# COF.net
KiCad netlist of a schematic drawn in Altium Designer
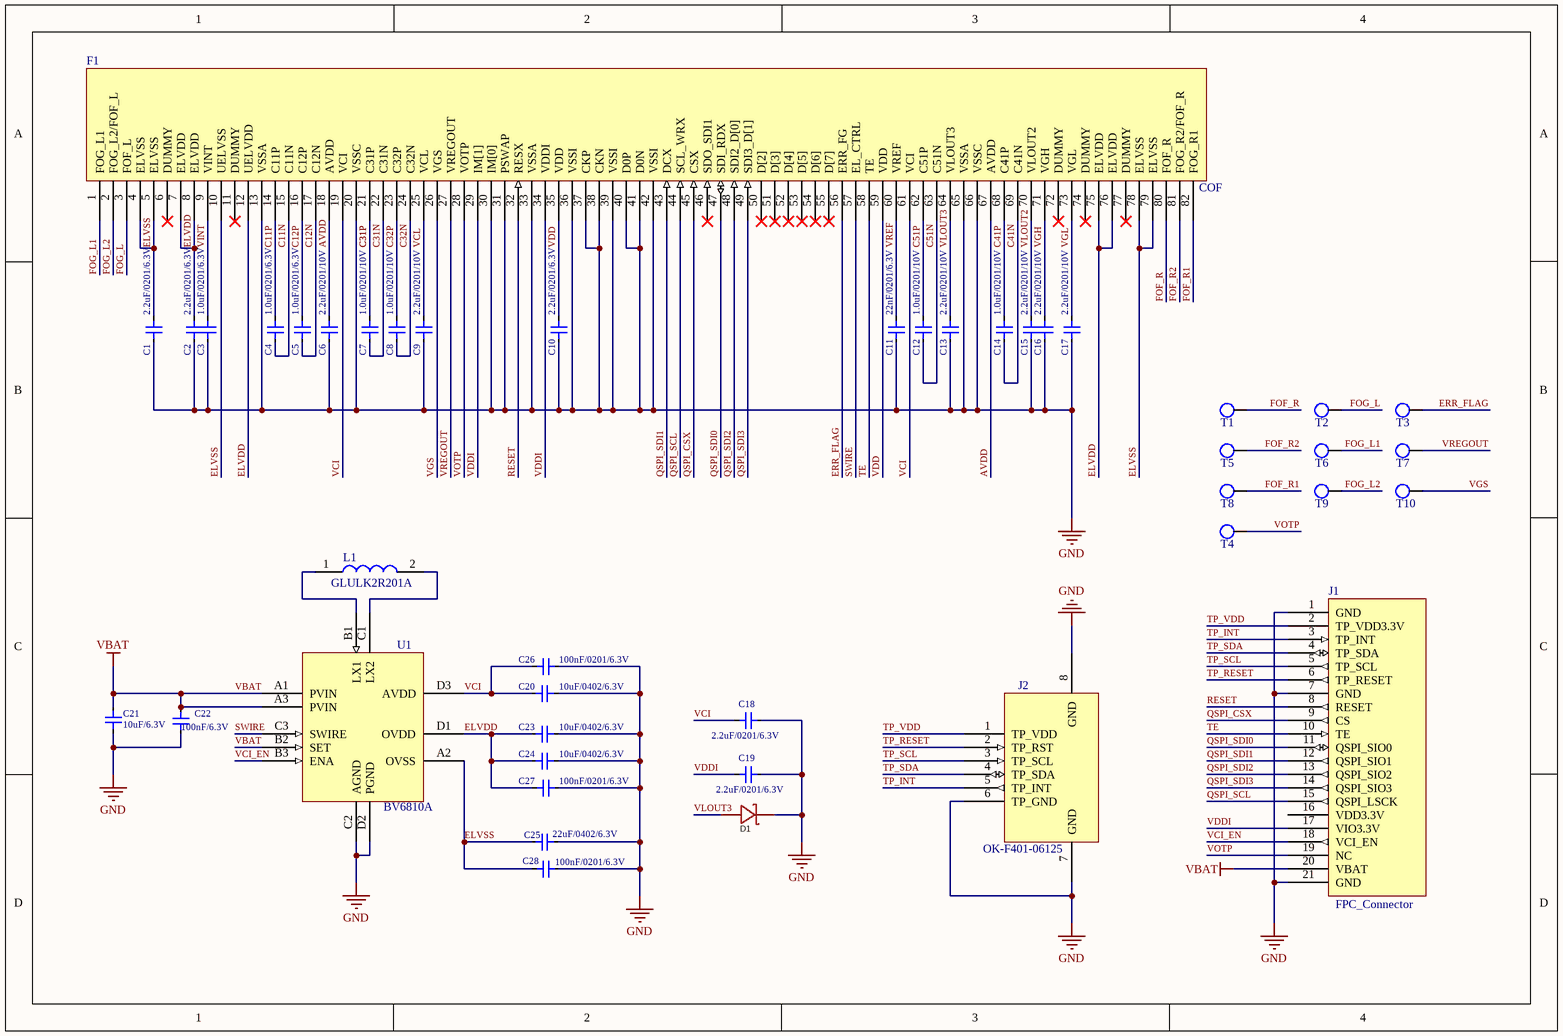
[diagram p0: COF.SchDoc]

(export (version "E")
  (design (tool "Eeschema 10.0.6"))
  (components
    (comp (ref "C1")
      (value "2.2uF/0201/6.3V")
      (footprint "CAPC0603X33N")
      (description "NONE")
      (fields
        (field (name "MANUFACTURER") "Murata")
        (field (name "MANUFACTURER PART NUMBER") "GRM033R61A105ME15D")
      )
      (libsource (lib "COF") (part "Capacitor"))
    )
    (comp (ref "C2")
      (value "2.2uF/0201/6.3V")
      (footprint "CAPC0603X33N")
      (description "NONE")
      (fields
        (field (name "MANUFACTURER") "Murata")
        (field (name "MANUFACTURER PART NUMBER") "GRM033R61A105ME15D")
      )
      (libsource (lib "COF") (part "Capacitor"))
    )
    (comp (ref "C3")
      (value "1.0uF/0201/6.3V")
      (footprint "CAPC0603X33N")
      (description "NONE")
      (fields
        (field (name "MANUFACTURER") "Murata")
        (field (name "MANUFACTURER PART NUMBER") "GRM033R61A105ME15D")
      )
      (libsource (lib "COF") (part "Capacitor"))
    )
    (comp (ref "C4")
      (value "1.0uF/0201/6.3V")
      (footprint "CAPC0603X33N")
      (description "NONE")
      (fields
        (field (name "MANUFACTURER") "Murata")
        (field (name "MANUFACTURER PART NUMBER") "GRM033R61A105ME15D")
      )
      (libsource (lib "COF") (part "Capacitor"))
    )
    (comp (ref "C5")
      (value "1.0uF/0201/6.3V")
      (footprint "CAPC0603X33N")
      (description "NONE")
      (fields
        (field (name "MANUFACTURER") "Murata")
        (field (name "MANUFACTURER PART NUMBER") "GRM033R61A105ME15D")
      )
      (libsource (lib "COF") (part "Capacitor"))
    )
    (comp (ref "C6")
      (value "2.2uF/0201/10V")
      (footprint "CAPC0603X33N")
      (description "NONE")
      (fields
        (field (name "MANUFACTURER") "Murata")
        (field (name "MANUFACTURER PART NUMBER") "GRM033R61A105ME15D")
      )
      (libsource (lib "COF") (part "Capacitor"))
    )
    (comp (ref "C7")
      (value "1.0uF/0201/10V")
      (footprint "CAPC0603X33N")
      (description "NONE")
      (fields
        (field (name "MANUFACTURER") "Murata")
        (field (name "MANUFACTURER PART NUMBER") "GRM033R61A105ME15D")
      )
      (libsource (lib "COF") (part "Capacitor"))
    )
    (comp (ref "C8")
      (value "1.0uF/0201/10V")
      (footprint "CAPC0603X33N")
      (description "NONE")
      (fields
        (field (name "MANUFACTURER") "Murata")
        (field (name "MANUFACTURER PART NUMBER") "GRM033R61A105ME15D")
      )
      (libsource (lib "COF") (part "Capacitor"))
    )
    (comp (ref "C9")
      (value "2.2uF/0201/10V")
      (footprint "CAPC0603X33N")
      (description "NONE")
      (fields
        (field (name "MANUFACTURER") "Murata")
        (field (name "MANUFACTURER PART NUMBER") "GRM033R61A105ME15D")
      )
      (libsource (lib "COF") (part "Capacitor"))
    )
    (comp (ref "C10")
      (value "2.2uF/0201/6.3V")
      (footprint "CAPC0603X33N")
      (description "NONE")
      (fields
        (field (name "MANUFACTURER") "Murata")
        (field (name "MANUFACTURER PART NUMBER") "GRM033R61A105ME15D")
      )
      (libsource (lib "COF") (part "Capacitor"))
    )
    (comp (ref "C11")
      (value "22nF/0201/6.3V")
      (footprint "CAPC0603X33N")
      (description "NONE")
      (fields
        (field (name "MANUFACTURER") "Murata")
        (field (name "MANUFACTURER PART NUMBER") "GRM033R61A105ME15D")
      )
      (libsource (lib "COF") (part "Capacitor"))
    )
    (comp (ref "C12")
      (value "1.0uF/0201/10V")
      (footprint "CAPC0603X33N")
      (description "NONE")
      (fields
        (field (name "MANUFACTURER") "Murata")
        (field (name "MANUFACTURER PART NUMBER") "GRM033R61A105ME15D")
      )
      (libsource (lib "COF") (part "Capacitor"))
    )
    (comp (ref "C13")
      (value "2.2uF/0201/10V")
      (footprint "CAPC0603X33N")
      (description "NONE")
      (fields
        (field (name "MANUFACTURER") "Murata")
        (field (name "MANUFACTURER PART NUMBER") "GRM033R61A105ME15D")
      )
      (libsource (lib "COF") (part "Capacitor"))
    )
    (comp (ref "C14")
      (value "1.0uF/0201/10V")
      (footprint "CAPC0603X33N")
      (description "NONE")
      (fields
        (field (name "MANUFACTURER") "Murata")
        (field (name "MANUFACTURER PART NUMBER") "GRM033R61A105ME15D")
      )
      (libsource (lib "COF") (part "Capacitor"))
    )
    (comp (ref "C15")
      (value "2.2uF/0201/10V")
      (footprint "CAPC0603X33N")
      (description "NONE")
      (fields
        (field (name "MANUFACTURER") "Murata")
        (field (name "MANUFACTURER PART NUMBER") "GRM033R61A105ME15D")
      )
      (libsource (lib "COF") (part "Capacitor"))
    )
    (comp (ref "C16")
      (value "2.2uF/0201/10V")
      (footprint "CAPC0603X33N")
      (description "NONE")
      (fields
        (field (name "MANUFACTURER") "Murata")
        (field (name "MANUFACTURER PART NUMBER") "GRM033R61A105ME15D")
      )
      (libsource (lib "COF") (part "Capacitor"))
    )
    (comp (ref "C17")
      (value "2.2uF/0201/10V")
      (footprint "CAPC0603X33N")
      (description "NONE")
      (fields
        (field (name "MANUFACTURER") "Murata")
        (field (name "MANUFACTURER PART NUMBER") "GRM033R61A105ME15D")
      )
      (libsource (lib "COF") (part "Capacitor"))
    )
    (comp (ref "C18")
      (value "2.2uF/0201/6.3V")
      (footprint "CAPC0603X33N")
      (description "NONE")
      (fields
        (field (name "MANUFACTURER") "Murata")
        (field (name "MANUFACTURER PART NUMBER") "GRM033R61A105ME15D")
      )
      (libsource (lib "COF") (part "Capacitor"))
    )
    (comp (ref "C19")
      (value "2.2uF/0201/6.3V")
      (footprint "CAPC0603X33N")
      (description "NONE")
      (fields
        (field (name "MANUFACTURER") "Murata")
        (field (name "MANUFACTURER PART NUMBER") "GRM033R61A105ME15D")
      )
      (libsource (lib "COF") (part "Capacitor"))
    )
    (comp (ref "C20")
      (value "10uF/0402/6.3V")
      (footprint "CAPC1005X57N")
      (description "NONE")
      (fields
        (field (name "MANUFACTURER") "Murata")
        (field (name "MANUFACTURER PART NUMBER") "GRM033R61A105ME15D")
      )
      (libsource (lib "COF") (part "Capacitor"))
    )
    (comp (ref "C21")
      (value "10uF/6.3V")
      (footprint "CAPC1005X57N")
      (description "NONE")
      (fields
        (field (name "MANUFACTURER") "Murata")
        (field (name "MANUFACTURER PART NUMBER") "GRM033R61A105ME15D")
      )
      (libsource (lib "COF") (part "Capacitor"))
    )
    (comp (ref "C22")
      (value "100nF/6.3V")
      (footprint "CAPC0603X33N")
      (description "NONE")
      (fields
        (field (name "MANUFACTURER") "Murata")
        (field (name "MANUFACTURER PART NUMBER") "GRM033R61A105ME15D")
      )
      (libsource (lib "COF") (part "Capacitor"))
    )
    (comp (ref "C23")
      (value "10uF/0402/6.3V")
      (footprint "CAPC1005X57N")
      (description "NONE")
      (fields
        (field (name "MANUFACTURER") "Murata")
        (field (name "MANUFACTURER PART NUMBER") "GRM033R61A105ME15D")
      )
      (libsource (lib "COF") (part "Capacitor"))
    )
    (comp (ref "C24")
      (value "10uF/0402/6.3V")
      (footprint "CAPC1005X57N")
      (description "NONE")
      (fields
        (field (name "MANUFACTURER") "Murata")
        (field (name "MANUFACTURER PART NUMBER") "GRM033R61A105ME15D")
      )
      (libsource (lib "COF") (part "Capacitor"))
    )
    (comp (ref "C25")
      (value "22uF/0402/6.3V")
      (footprint "CAPC1005X57N")
      (description "NONE")
      (fields
        (field (name "MANUFACTURER") "Murata")
        (field (name "MANUFACTURER PART NUMBER") "GRM033R61A105ME15D")
      )
      (libsource (lib "COF") (part "Capacitor"))
    )
    (comp (ref "C26")
      (value "100nF/0201/6.3V")
      (footprint "CAPC0603X33N")
      (description "NONE")
      (fields
        (field (name "MANUFACTURER") "Murata")
        (field (name "MANUFACTURER PART NUMBER") "GRM033R61A105ME15D")
      )
      (libsource (lib "COF") (part "Capacitor"))
    )
    (comp (ref "C27")
      (value "100nF/0201/6.3V")
      (footprint "CAPC0603X33N")
      (description "NONE")
      (fields
        (field (name "MANUFACTURER") "Murata")
        (field (name "MANUFACTURER PART NUMBER") "GRM033R61A105ME15D")
      )
      (libsource (lib "COF") (part "Capacitor"))
    )
    (comp (ref "C28")
      (value "100nF/0201/6.3V")
      (footprint "CAPC0603X33N")
      (description "NONE")
      (fields
        (field (name "MANUFACTURER") "Murata")
        (field (name "MANUFACTURER PART NUMBER") "GRM033R61A105ME15D")
      )
      (libsource (lib "COF") (part "Capacitor"))
    )
    (comp (ref "D1")
      (value "LDSR01S30ST5G")
      (footprint "DFN0603-D_L0.6-W0.3-P0.34-RD")
      (fields (field (name "MANUFACTURER") "LRC(乐山无线电)"))
      (libsource (lib "COF") (part "LDSR01S30ST5G"))
    )
    (comp (ref "F1") (value "COF") (footprint "COF Connector") (libsource (lib "COF") (part "COF")))
    (comp (ref "J1")
      (value "FPC_Connector")
      (footprint "FPC Connector")
      (libsource (lib "COF") (part "21Pin_Connector"))
    )
    (comp (ref "J2")
      (value "OK-F401-06125")
      (footprint "FFC-SMD_6P-P0.50_FH34SRJ-6S-0.5SH")
      (libsource (lib "COF") (part "OK-F401-06125"))
    )
    (comp (ref "L1")
      (value "GLULK2R201A")
      (footprint "MPL2012S2R2MDT")
      (description "Inductor")
      (fields
        (field (name "MANUFACTURER_PART_NUMBER") "LQM2MPN2R2NG0L")
        (field (name "MOUSER PART NUMBER") "81-LQM2MPN2R2NG0L")
      )
      (libsource (lib "COF") (part "GLULK2R201A"))
    )
    (comp (ref "T1")
      (value "Test_Point")
      (footprint "TP-C045-PI")
      (libsource (lib "COF") (part "Test_Point"))
    )
    (comp (ref "T2")
      (value "Test_Point")
      (footprint "TP-C045-PI")
      (libsource (lib "COF") (part "Test_Point"))
    )
    (comp (ref "T3")
      (value "Test_Point")
      (footprint "TP-C045-PI")
      (libsource (lib "COF") (part "Test_Point"))
    )
    (comp (ref "T4")
      (value "Test_Point")
      (footprint "TP-C045-PI")
      (libsource (lib "COF") (part "Test_Point"))
    )
    (comp (ref "T5")
      (value "Test_Point")
      (footprint "TP-C045-PI")
      (libsource (lib "COF") (part "Test_Point"))
    )
    (comp (ref "T6")
      (value "Test_Point")
      (footprint "TP-C045-PI")
      (libsource (lib "COF") (part "Test_Point"))
    )
    (comp (ref "T7")
      (value "Test_Point")
      (footprint "TP-C045-PI")
      (libsource (lib "COF") (part "Test_Point"))
    )
    (comp (ref "T8")
      (value "Test_Point")
      (footprint "TP-C045-PI")
      (libsource (lib "COF") (part "Test_Point"))
    )
    (comp (ref "T9")
      (value "Test_Point")
      (footprint "TP-C045-PI")
      (libsource (lib "COF") (part "Test_Point"))
    )
    (comp (ref "T10")
      (value "Test_Point")
      (footprint "TP-C045-PI")
      (libsource (lib "COF") (part "Test_Point"))
    )
    (comp (ref "U1")
      (value "BV6810A")
      (footprint "WLCSP-12_L1.7-W1.5-R4-C3-P0.40-TL-1")
      (libsource (lib "COF") (part "BV6810A"))
    )
  )
  (nets
    (net (code "1") (name "/AVDD") (class "Default")
      (node (ref "C6") (pin "1") (pinfunction "1_1") (pintype "passive"))
      (node (ref "F1") (pin "18") (pinfunction "AVDD_18") (pintype "power_in"))
      (node (ref "F1") (pin "67") (pinfunction "AVDD_67") (pintype "power_in"))
    )
    (net (code "2") (name "/C11N") (class "Default")
      (node (ref "C4") (pin "2") (pinfunction "2_2") (pintype "passive"))
      (node (ref "F1") (pin "15") (pinfunction "C11N_15") (pintype "tri_state"))
    )
    (net (code "3") (name "/C11P") (class "Default")
      (node (ref "C4") (pin "1") (pinfunction "1_1") (pintype "passive"))
      (node (ref "F1") (pin "14") (pinfunction "C11P_14") (pintype "tri_state"))
    )
    (net (code "4") (name "/C12N") (class "Default")
      (node (ref "C5") (pin "2") (pinfunction "2_2") (pintype "passive"))
      (node (ref "F1") (pin "17") (pinfunction "C12N_17") (pintype "tri_state"))
    )
    (net (code "5") (name "/C12P") (class "Default")
      (node (ref "C5") (pin "1") (pinfunction "1_1") (pintype "passive"))
      (node (ref "F1") (pin "16") (pinfunction "C12P_16") (pintype "tri_state"))
    )
    (net (code "6") (name "/C31N") (class "Default")
      (node (ref "C7") (pin "2") (pinfunction "2_2") (pintype "passive"))
      (node (ref "F1") (pin "22") (pinfunction "C31N_22") (pintype "tri_state"))
    )
    (net (code "7") (name "/C31P") (class "Default")
      (node (ref "C7") (pin "1") (pinfunction "1_1") (pintype "passive"))
      (node (ref "F1") (pin "21") (pinfunction "C31P_21") (pintype "tri_state"))
    )
    (net (code "8") (name "/C32N") (class "Default")
      (node (ref "C8") (pin "2") (pinfunction "2_2") (pintype "passive"))
      (node (ref "F1") (pin "24") (pinfunction "C32N_24") (pintype "tri_state"))
    )
    (net (code "9") (name "/C32P") (class "Default")
      (node (ref "C8") (pin "1") (pinfunction "1_1") (pintype "passive"))
      (node (ref "F1") (pin "23") (pinfunction "C32P_23") (pintype "tri_state"))
    )
    (net (code "10") (name "/C41N") (class "Default")
      (node (ref "C14") (pin "2") (pinfunction "2_2") (pintype "passive"))
      (node (ref "F1") (pin "69") (pinfunction "C41N_69") (pintype "tri_state"))
    )
    (net (code "11") (name "/C41P") (class "Default")
      (node (ref "C14") (pin "1") (pinfunction "1_1") (pintype "passive"))
      (node (ref "F1") (pin "68") (pinfunction "C41P_68") (pintype "tri_state"))
    )
    (net (code "12") (name "/C51N") (class "Default")
      (node (ref "C12") (pin "2") (pinfunction "2_2") (pintype "passive"))
      (node (ref "F1") (pin "63") (pinfunction "C51N_63") (pintype "tri_state"))
    )
    (net (code "13") (name "/C51P") (class "Default")
      (node (ref "C12") (pin "1") (pinfunction "1_1") (pintype "passive"))
      (node (ref "F1") (pin "62") (pinfunction "C51P_62") (pintype "tri_state"))
    )
    (net (code "14") (name "/ELVDD") (class "Default")
      (node (ref "C2") (pin "1") (pinfunction "1_1") (pintype "passive"))
      (node (ref "C23") (pin "2") (pinfunction "2_2") (pintype "passive"))
      (node (ref "C24") (pin "2") (pinfunction "2_2") (pintype "passive"))
      (node (ref "C27") (pin "1") (pinfunction "1_1") (pintype "passive"))
      (node (ref "F1") (pin "12") (pinfunction "UELVDD_12") (pintype "power_in"))
      (node (ref "F1") (pin "7") (pinfunction "ELVDD_7") (pintype "power_in"))
      (node (ref "F1") (pin "75") (pinfunction "ELVDD_75") (pintype "power_in"))
      (node (ref "F1") (pin "76") (pinfunction "ELVDD_76") (pintype "power_in"))
      (node (ref "F1") (pin "8") (pinfunction "ELVDD_8") (pintype "power_in"))
      (node (ref "U1") (pin "D1") (pinfunction "OVDD_D1") (pintype "power_in"))
    )
    (net (code "15") (name "/ELVSS") (class "Default")
      (node (ref "C1") (pin "1") (pinfunction "1_1") (pintype "passive"))
      (node (ref "C25") (pin "2") (pinfunction "2_2") (pintype "passive"))
      (node (ref "C28") (pin "1") (pinfunction "1_1") (pintype "passive"))
      (node (ref "F1") (pin "10") (pinfunction "UELVSS_10") (pintype "power_in"))
      (node (ref "F1") (pin "4") (pinfunction "ELVSS_4") (pintype "power_in"))
      (node (ref "F1") (pin "5") (pinfunction "ELVSS_5") (pintype "power_in"))
      (node (ref "F1") (pin "78") (pinfunction "ELVSS_78") (pintype "power_in"))
      (node (ref "F1") (pin "79") (pinfunction "ELVSS_79") (pintype "power_in"))
      (node (ref "U1") (pin "A2") (pinfunction "OVSS_A2") (pintype "power_in"))
    )
    (net (code "16") (name "/ERR_FLAG") (class "Default")
      (node (ref "F1") (pin "56") (pinfunction "ERR_FG_56") (pintype "tri_state"))
      (node (ref "T3") (pin "1") (pinfunction "1_1") (pintype "passive"))
    )
    (net (code "17") (name "/FOF_R") (class "Default")
      (node (ref "F1") (pin "80") (pinfunction "FOF_R_80") (pintype "tri_state"))
      (node (ref "T1") (pin "1") (pinfunction "1_1") (pintype "passive"))
    )
    (net (code "18") (name "/FOF_R1") (class "Default")
      (node (ref "F1") (pin "82") (pinfunction "FOG_R1_82") (pintype "tri_state"))
      (node (ref "T8") (pin "1") (pinfunction "1_1") (pintype "passive"))
    )
    (net (code "19") (name "/FOF_R2") (class "Default")
      (node (ref "F1") (pin "81") (pinfunction "FOG_R2/FOF_R_81") (pintype "tri_state"))
      (node (ref "T5") (pin "1") (pinfunction "1_1") (pintype "passive"))
    )
    (net (code "20") (name "/FOG_L") (class "Default")
      (node (ref "F1") (pin "3") (pinfunction "FOF_L_3") (pintype "tri_state"))
      (node (ref "T2") (pin "1") (pinfunction "1_1") (pintype "passive"))
    )
    (net (code "21") (name "/FOG_L1") (class "Default")
      (node (ref "F1") (pin "1") (pinfunction "FOG_L1_1") (pintype "tri_state"))
      (node (ref "T6") (pin "1") (pinfunction "1_1") (pintype "passive"))
    )
    (net (code "22") (name "/FOG_L2") (class "Default")
      (node (ref "F1") (pin "2") (pinfunction "FOG_L2/FOF_L_2") (pintype "tri_state"))
      (node (ref "T9") (pin "1") (pinfunction "1_1") (pintype "passive"))
    )
    (net (code "23") (name "/QSPI_CSX") (class "Default")
      (node (ref "F1") (pin "45") (pinfunction "CSX_45") (pintype "input"))
      (node (ref "J1") (pin "9") (pinfunction "CS_9") (pintype "output"))
    )
    (net (code "24") (name "/QSPI_SCL") (class "Default")
      (node (ref "F1") (pin "44") (pinfunction "SCL_WRX_44") (pintype "input"))
      (node (ref "J1") (pin "15") (pinfunction "QSPI_LSCK_15") (pintype "output"))
    )
    (net (code "25") (name "/QSPI_SDI0") (class "Default")
      (node (ref "F1") (pin "47") (pinfunction "SDI_RDX_47") (pintype "bidirectional"))
      (node (ref "J1") (pin "11") (pinfunction "QSPI_SIO0_11") (pintype "bidirectional"))
    )
    (net (code "26") (name "/QSPI_SDI1") (class "Default")
      (node (ref "F1") (pin "43") (pinfunction "DCX_43") (pintype "input"))
      (node (ref "J1") (pin "12") (pinfunction "QSPI_SIO1_12") (pintype "output"))
    )
    (net (code "27") (name "/QSPI_SDI2") (class "Default")
      (node (ref "F1") (pin "48") (pinfunction "SDI2_D[0]_48") (pintype "input"))
      (node (ref "J1") (pin "13") (pinfunction "QSPI_SIO2_13") (pintype "output"))
    )
    (net (code "28") (name "/QSPI_SDI3") (class "Default")
      (node (ref "F1") (pin "49") (pinfunction "SDI3_D[1]_49") (pintype "input"))
      (node (ref "J1") (pin "14") (pinfunction "QSPI_SIO3_14") (pintype "output"))
    )
    (net (code "29") (name "/RESET") (class "Default")
      (node (ref "F1") (pin "32") (pinfunction "RESX_32") (pintype "input"))
      (node (ref "J1") (pin "8") (pinfunction "RESET_8") (pintype "output"))
    )
    (net (code "30") (name "/SWIRE") (class "Default")
      (node (ref "F1") (pin "57") (pinfunction "EL_CTRL_57") (pintype "tri_state"))
      (node (ref "U1") (pin "C3") (pinfunction "SWIRE_C3") (pintype "input"))
    )
    (net (code "31") (name "/TE") (class "Default")
      (node (ref "F1") (pin "58") (pinfunction "TE_58") (pintype "tri_state"))
      (node (ref "J1") (pin "10") (pinfunction "TE_10") (pintype "input"))
    )
    (net (code "32") (name "/TP_INT") (class "Default")
      (node (ref "J1") (pin "3") (pinfunction "TP_INT_3") (pintype "input"))
      (node (ref "J2") (pin "5") (pinfunction "TP_INT_5") (pintype "output"))
    )
    (net (code "33") (name "/TP_RESET") (class "Default")
      (node (ref "J1") (pin "6") (pinfunction "TP_RESET_6") (pintype "output"))
      (node (ref "J2") (pin "2") (pinfunction "TP_RST_2") (pintype "input"))
    )
    (net (code "34") (name "/TP_SCL") (class "Default")
      (node (ref "J1") (pin "5") (pinfunction "TP_SCL_5") (pintype "output"))
      (node (ref "J2") (pin "3") (pinfunction "TP_SCL_3") (pintype "input"))
    )
    (net (code "35") (name "/TP_SDA") (class "Default")
      (node (ref "J1") (pin "4") (pinfunction "TP_SDA_4") (pintype "bidirectional"))
      (node (ref "J2") (pin "4") (pinfunction "TP_SDA_4") (pintype "bidirectional"))
    )
    (net (code "36") (name "/TP_VDD") (class "Default")
      (node (ref "J1") (pin "2") (pinfunction "TP_VDD3.3V_2") (pintype "power_in"))
      (node (ref "J2") (pin "1") (pinfunction "TP_VDD_1") (pintype "power_in"))
    )
    (net (code "37") (name "/VCI") (class "Default")
      (node (ref "C18") (pin "1") (pinfunction "1_1") (pintype "passive"))
      (node (ref "C20") (pin "2") (pinfunction "2_2") (pintype "passive"))
      (node (ref "C26") (pin "1") (pinfunction "1_1") (pintype "passive"))
      (node (ref "F1") (pin "19") (pinfunction "VCI_19") (pintype "power_in"))
      (node (ref "F1") (pin "61") (pinfunction "VCI_61") (pintype "power_in"))
      (node (ref "U1") (pin "D3") (pinfunction "AVDD_D3") (pintype "power_in"))
    )
    (net (code "38") (name "/VCI_EN") (class "Default")
      (node (ref "J1") (pin "18") (pinfunction "VCI_EN_18") (pintype "output"))
      (node (ref "U1") (pin "B3") (pinfunction "ENA_B3") (pintype "input"))
    )
    (net (code "39") (name "/VCL") (class "Default")
      (node (ref "C9") (pin "1") (pinfunction "1_1") (pintype "passive"))
      (node (ref "F1") (pin "25") (pinfunction "VCL_25") (pintype "power_in"))
    )
    (net (code "40") (name "/VDD") (class "Default")
      (node (ref "C10") (pin "1") (pinfunction "1_1") (pintype "passive"))
      (node (ref "F1") (pin "35") (pinfunction "VDD_35") (pintype "power_in"))
      (node (ref "F1") (pin "59") (pinfunction "VDD_59") (pintype "power_in"))
    )
    (net (code "41") (name "/VDDI") (class "Default")
      (node (ref "C19") (pin "1") (pinfunction "1_1") (pintype "passive"))
      (node (ref "F1") (pin "29") (pinfunction "IM[1]_29") (pintype "passive"))
      (node (ref "F1") (pin "34") (pinfunction "VDDI_34") (pintype "power_in"))
      (node (ref "J1") (pin "17") (pinfunction "VIO3.3V_17") (pintype "power_in"))
    )
    (net (code "42") (name "/VGH") (class "Default")
      (node (ref "C16") (pin "1") (pinfunction "1_1") (pintype "passive"))
      (node (ref "F1") (pin "71") (pinfunction "VGH_71") (pintype "tri_state"))
    )
    (net (code "43") (name "/VGL") (class "Default")
      (node (ref "C17") (pin "1") (pinfunction "1_1") (pintype "passive"))
      (node (ref "F1") (pin "73") (pinfunction "VGL_73") (pintype "power_in"))
    )
    (net (code "44") (name "/VGS") (class "Default")
      (node (ref "F1") (pin "26") (pinfunction "VGS_26") (pintype "power_in"))
      (node (ref "T10") (pin "1") (pinfunction "1_1") (pintype "passive"))
    )
    (net (code "45") (name "/VINT") (class "Default")
      (node (ref "C3") (pin "1") (pinfunction "1_1") (pintype "passive"))
      (node (ref "F1") (pin "9") (pinfunction "VINT_9") (pintype "tri_state"))
    )
    (net (code "46") (name "/VLOUT2") (class "Default")
      (node (ref "C15") (pin "1") (pinfunction "1_1") (pintype "passive"))
      (node (ref "F1") (pin "70") (pinfunction "VLOUT2_70") (pintype "power_in"))
    )
    (net (code "47") (name "/VLOUT3") (class "Default")
      (node (ref "C13") (pin "1") (pinfunction "1_1") (pintype "passive"))
      (node (ref "D1") (pin "2") (pinfunction "A_2") (pintype "passive"))
      (node (ref "F1") (pin "64") (pinfunction "VLOUT3_64") (pintype "power_in"))
    )
    (net (code "48") (name "/VOTP") (class "Default")
      (node (ref "F1") (pin "28") (pinfunction "VOTP_28") (pintype "power_in"))
      (node (ref "J1") (pin "19") (pinfunction "NC_19") (pintype "passive"))
      (node (ref "T4") (pin "1") (pinfunction "1_1") (pintype "passive"))
    )
    (net (code "49") (name "/VREF") (class "Default")
      (node (ref "C11") (pin "1") (pinfunction "1_1") (pintype "passive"))
      (node (ref "F1") (pin "60") (pinfunction "VREF_60") (pintype "power_in"))
    )
    (net (code "50") (name "/VREGOUT") (class "Default")
      (node (ref "F1") (pin "27") (pinfunction "VREGOUT_27") (pintype "power_in"))
      (node (ref "T7") (pin "1") (pinfunction "1_1") (pintype "passive"))
    )
    (net (code "51") (name "GND") (class "Default")
      (node (ref "C1") (pin "2") (pinfunction "2_2") (pintype "passive"))
      (node (ref "C10") (pin "2") (pinfunction "2_2") (pintype "passive"))
      (node (ref "C11") (pin "2") (pinfunction "2_2") (pintype "passive"))
      (node (ref "C13") (pin "2") (pinfunction "2_2") (pintype "passive"))
      (node (ref "C15") (pin "2") (pinfunction "2_2") (pintype "passive"))
      (node (ref "C16") (pin "2") (pinfunction "2_2") (pintype "passive"))
      (node (ref "C17") (pin "2") (pinfunction "2_2") (pintype "passive"))
      (node (ref "C18") (pin "2") (pinfunction "2_2") (pintype "passive"))
      (node (ref "C19") (pin "2") (pinfunction "2_2") (pintype "passive"))
      (node (ref "C2") (pin "2") (pinfunction "2_2") (pintype "passive"))
      (node (ref "C20") (pin "1") (pinfunction "1_1") (pintype "passive"))
      (node (ref "C21") (pin "1") (pinfunction "1_1") (pintype "passive"))
      (node (ref "C22") (pin "2") (pinfunction "2_2") (pintype "passive"))
      (node (ref "C23") (pin "1") (pinfunction "1_1") (pintype "passive"))
      (node (ref "C24") (pin "1") (pinfunction "1_1") (pintype "passive"))
      (node (ref "C25") (pin "1") (pinfunction "1_1") (pintype "passive"))
      (node (ref "C26") (pin "2") (pinfunction "2_2") (pintype "passive"))
      (node (ref "C27") (pin "2") (pinfunction "2_2") (pintype "passive"))
      (node (ref "C28") (pin "2") (pinfunction "2_2") (pintype "passive"))
      (node (ref "C3") (pin "2") (pinfunction "2_2") (pintype "passive"))
      (node (ref "C6") (pin "2") (pinfunction "2_2") (pintype "passive"))
      (node (ref "C9") (pin "2") (pinfunction "2_2") (pintype "passive"))
      (node (ref "D1") (pin "1") (pinfunction "C_1") (pintype "passive"))
      (node (ref "F1") (pin "13") (pinfunction "VSSA_13") (pintype "power_in"))
      (node (ref "F1") (pin "20") (pinfunction "VSSC_20") (pintype "power_in"))
      (node (ref "F1") (pin "30") (pinfunction "IM[0]_30") (pintype "passive"))
      (node (ref "F1") (pin "31") (pinfunction "PSWAP_31") (pintype "passive"))
      (node (ref "F1") (pin "33") (pinfunction "VSSA_33") (pintype "power_in"))
      (node (ref "F1") (pin "36") (pinfunction "VSSI_36") (pintype "power_in"))
      (node (ref "F1") (pin "37") (pinfunction "CKP_37") (pintype "passive"))
      (node (ref "F1") (pin "38") (pinfunction "CKN_38") (pintype "passive"))
      (node (ref "F1") (pin "39") (pinfunction "VSSI_39") (pintype "power_in"))
      (node (ref "F1") (pin "40") (pinfunction "D0P_40") (pintype "passive"))
      (node (ref "F1") (pin "41") (pinfunction "D0N_41") (pintype "passive"))
      (node (ref "F1") (pin "42") (pinfunction "VSSI_42") (pintype "power_in"))
      (node (ref "F1") (pin "65") (pinfunction "VSSA_65") (pintype "power_in"))
      (node (ref "F1") (pin "66") (pinfunction "VSSC_66") (pintype "power_in"))
      (node (ref "J1") (pin "1") (pinfunction "GND_1") (pintype "power_in"))
      (node (ref "J1") (pin "21") (pinfunction "GND_21") (pintype "power_in"))
      (node (ref "J1") (pin "7") (pinfunction "GND_7") (pintype "power_in"))
      (node (ref "J2") (pin "6") (pinfunction "TP_GND_6") (pintype "power_in"))
      (node (ref "J2") (pin "7") (pinfunction "GND_7") (pintype "power_in"))
      (node (ref "J2") (pin "8") (pinfunction "GND_8") (pintype "power_in"))
      (node (ref "U1") (pin "C2") (pinfunction "AGND_C2") (pintype "power_in"))
      (node (ref "U1") (pin "D2") (pinfunction "PGND_D2") (pintype "power_in"))
    )
    (net (code "52") (name "Net-(U1-LX1)") (class "Default")
      (node (ref "L1") (pin "1") (pinfunction "1_1") (pintype "passive"))
      (node (ref "U1") (pin "B1") (pinfunction "LX1_B1") (pintype "input"))
    )
    (net (code "53") (name "Net-(U1-LX2)") (class "Default")
      (node (ref "L1") (pin "2") (pinfunction "2_2") (pintype "passive"))
      (node (ref "U1") (pin "C1") (pinfunction "LX2_C1") (pintype "tri_state"))
    )
    (net (code "54") (name "VBAT") (class "Default")
      (node (ref "C21") (pin "2") (pinfunction "2_2") (pintype "passive"))
      (node (ref "C22") (pin "1") (pinfunction "1_1") (pintype "passive"))
      (node (ref "J1") (pin "20") (pinfunction "VBAT_20") (pintype "power_in"))
      (node (ref "U1") (pin "A1") (pinfunction "PVIN_A1") (pintype "power_in"))
      (node (ref "U1") (pin "A3") (pinfunction "PVIN_A3") (pintype "power_in"))
      (node (ref "U1") (pin "B2") (pinfunction "SET_B2") (pintype "input"))
    )
    (net (code "55") (name "unconnected-(F1-DUMMY-Pad6)") (class "Default")
      (node (ref "F1") (pin "6") (pinfunction "DUMMY_6") (pintype "tri_state+no_connect"))
    )
    (net (code "56") (name "unconnected-(F1-DUMMY-Pad11)") (class "Default")
      (node (ref "F1") (pin "11") (pinfunction "DUMMY_11") (pintype "tri_state+no_connect"))
    )
    (net (code "57") (name "unconnected-(F1-DUMMY-Pad72)") (class "Default")
      (node (ref "F1") (pin "72") (pinfunction "DUMMY_72") (pintype "tri_state+no_connect"))
    )
    (net (code "58") (name "unconnected-(F1-DUMMY-Pad74)") (class "Default")
      (node (ref "F1") (pin "74") (pinfunction "DUMMY_74") (pintype "tri_state+no_connect"))
    )
    (net (code "59") (name "unconnected-(F1-DUMMY-Pad77)") (class "Default")
      (node (ref "F1") (pin "77") (pinfunction "DUMMY_77") (pintype "tri_state+no_connect"))
    )
    (net (code "60") (name "unconnected-(F1-D[2]-Pad50)") (class "Default")
      (node (ref "F1") (pin "50") (pinfunction "D[2]_50") (pintype "tri_state+no_connect"))
    )
    (net (code "61") (name "unconnected-(F1-D[3]-Pad51)") (class "Default")
      (node (ref "F1") (pin "51") (pinfunction "D[3]_51") (pintype "tri_state+no_connect"))
    )
    (net (code "62") (name "unconnected-(F1-D[4]-Pad52)") (class "Default")
      (node (ref "F1") (pin "52") (pinfunction "D[4]_52") (pintype "tri_state+no_connect"))
    )
    (net (code "63") (name "unconnected-(F1-D[5]-Pad53)") (class "Default")
      (node (ref "F1") (pin "53") (pinfunction "D[5]_53") (pintype "tri_state+no_connect"))
    )
    (net (code "64") (name "unconnected-(F1-D[6]-Pad54)") (class "Default")
      (node (ref "F1") (pin "54") (pinfunction "D[6]_54") (pintype "tri_state+no_connect"))
    )
    (net (code "65") (name "unconnected-(F1-D[7]-Pad55)") (class "Default")
      (node (ref "F1") (pin "55") (pinfunction "D[7]_55") (pintype "tri_state+no_connect"))
    )
    (net (code "66") (name "unconnected-(F1-SDO_SDI1-Pad46)") (class "Default")
      (node (ref "F1") (pin "46") (pinfunction "SDO_SDI1_46") (pintype "input+no_connect"))
    )
    (net (code "67") (name "unconnected-(J1-VDD3.3V-Pad16)") (class "Default")
      (node (ref "J1") (pin "16") (pinfunction "VDD3.3V_16") (pintype "power_in"))
    )
  )
)
